# stepdown.net
KiCad netlist of a schematic drawn in EAGLE
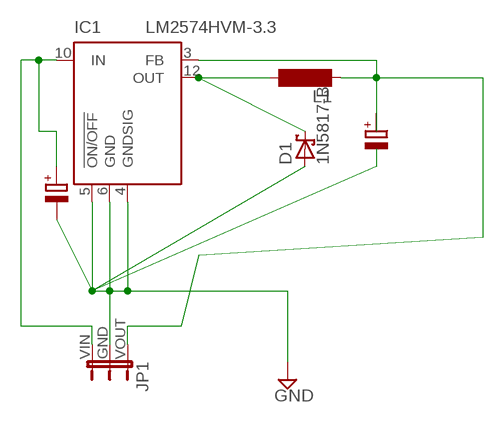
[diagram p0: schematic, sheet 1]

(export (version "E")
  (design (tool "Eeschema 10.0.6"))
  (components
    (comp (ref "D1")
      (value "1N5817-B")
      (footprint "eagle-import:DO41-7.6")
      (libsource (lib "eagle-import") (part "1N5817-B"))
    )
    (comp (ref "IC1")
      (value "LM2574HVM-3.3")
      (footprint "eagle-import:SO14W")
      (libsource (lib "eagle-import") (part "LM2574?-HVM3.3"))
    )
    (comp (ref "JP1")
      (value "JP2W")
      (footprint "eagle-import:JP2W")
      (libsource (lib "eagle-import") (part "JP2W"))
    )
    (comp (ref "L1")
      (value "SM-1206")
      (footprint "eagle-import:SM-1206")
      (libsource (lib "eagle-import") (part "SM-1206"))
    )
  )
  (nets
    (net (code "1") (name "GND") (class "Default")
      (node (ref "D1") (pin "A") (pinfunction "A_A") (pintype "passive"))
      (node (ref "IC1") (pin "4") (pinfunction "GNDSIG_4") (pintype "input"))
      (node (ref "IC1") (pin "5") (pinfunction "~{ON/OFF}_5") (pintype "input"))
      (node (ref "IC1") (pin "6") (pinfunction "GND_6") (pintype "power_in"))
      (node (ref "JP1") (pin "GND") (pinfunction "2_GND") (pintype "passive"))
    )
    (net (code "2") (name "Net-(IC1-FB)") (class "Default")
      (node (ref "IC1") (pin "3") (pinfunction "FB_3") (pintype "input"))
      (node (ref "JP1") (pin "VOUT") (pinfunction "1_VOUT") (pintype "passive"))
      (node (ref "L1") (pin "1") (pinfunction "1_1") (pintype "passive"))
    )
    (net (code "3") (name "Net-(IC1-IN)") (class "Default")
      (node (ref "IC1") (pin "10") (pinfunction "IN_10") (pintype "input"))
      (node (ref "JP1") (pin "VIN") (pinfunction "3_VIN") (pintype "passive"))
    )
    (net (code "4") (name "Net-(IC1-OUT)") (class "Default")
      (node (ref "D1") (pin "C") (pinfunction "C_C") (pintype "passive"))
      (node (ref "IC1") (pin "12") (pinfunction "OUT_12") (pintype "passive"))
      (node (ref "L1") (pin "2") (pinfunction "2_2") (pintype "passive"))
    )
  )
)
